# 4th_4G.net
KiCad netlist of a schematic drawn in Altium Designer
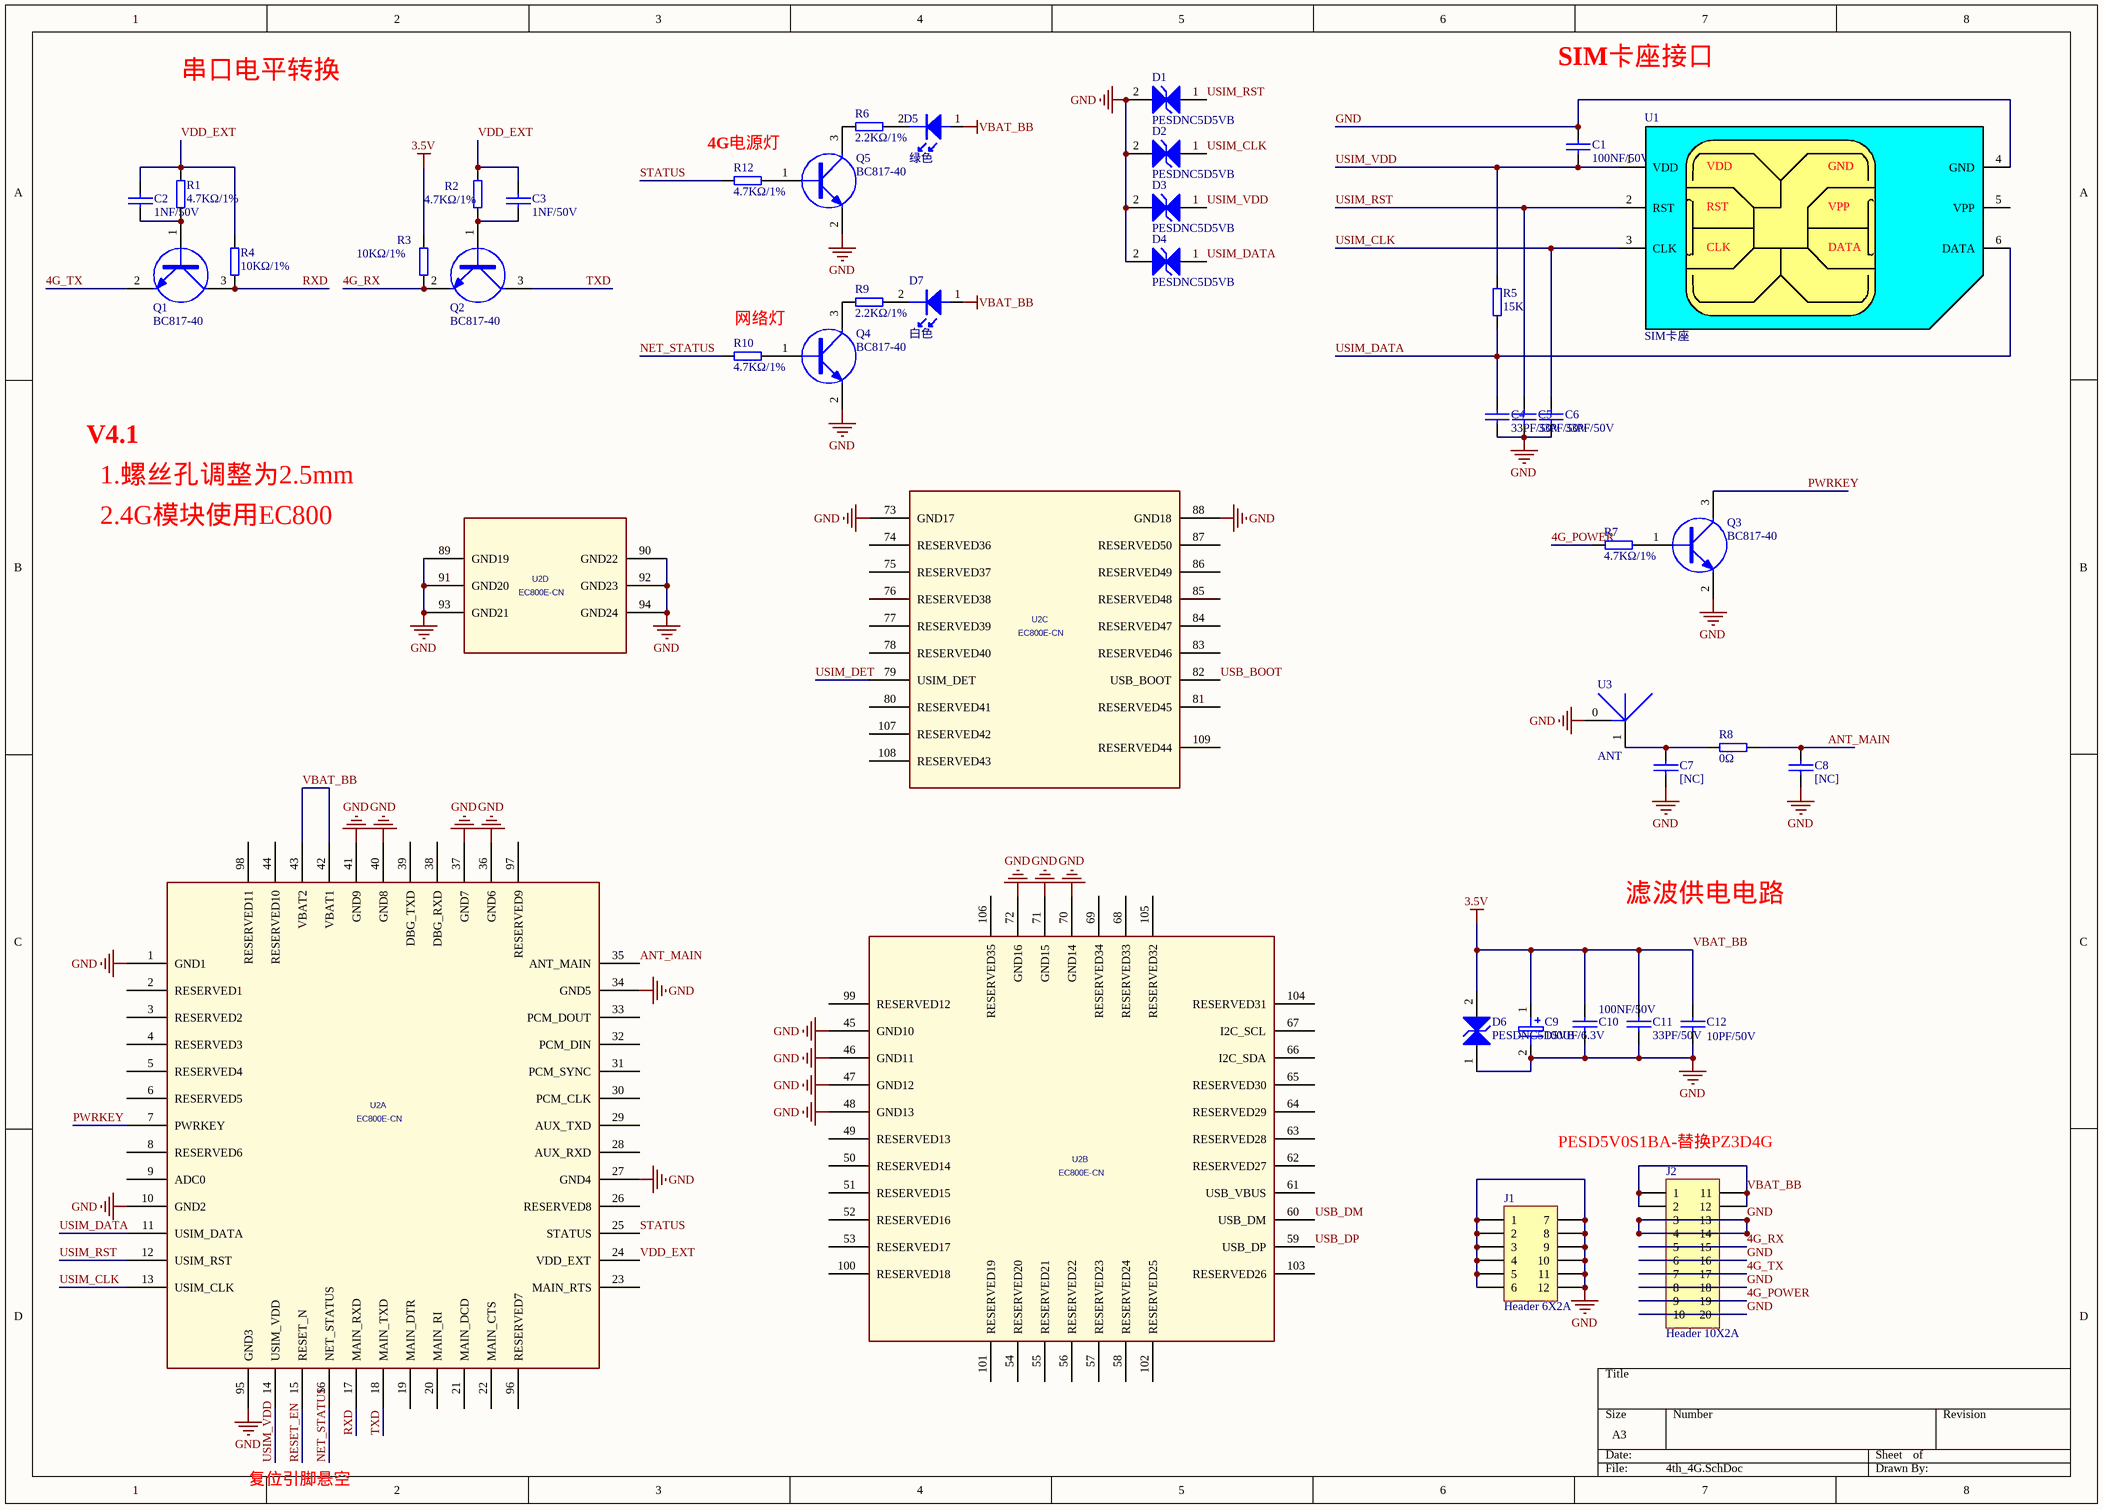
[diagram p0: 4th_4G.SchDoc]

(export (version "E")
  (design (tool "Eeschema 10.0.6"))
  (components
    (comp (ref "C1")
      (value "100NF/50V")
      (footprint "0603_C")
      (description "无极性电容")
      (libsource (lib "Integrated_Library") (part "CAP"))
    )
    (comp (ref "C2")
      (value "1NF/50V")
      (footprint "0603_C")
      (description "无极性电容")
      (libsource (lib "Integrated_Library") (part "CAP"))
    )
    (comp (ref "C3")
      (value "1NF/50V")
      (footprint "0603_C")
      (description "无极性电容")
      (libsource (lib "Integrated_Library") (part "CAP"))
    )
    (comp (ref "C4")
      (value "33PF/50V")
      (footprint "0603_C")
      (description "无极性电容")
      (libsource (lib "Integrated_Library") (part "CAP"))
    )
    (comp (ref "C5")
      (value "33PF/50V")
      (footprint "0603_C")
      (description "无极性电容")
      (libsource (lib "Integrated_Library") (part "CAP"))
    )
    (comp (ref "C6")
      (value "33PF/50V")
      (footprint "0603_C")
      (description "无极性电容")
      (libsource (lib "Integrated_Library") (part "CAP"))
    )
    (comp (ref "C7")
      (value "[NC]")
      (footprint "0603_C")
      (description "无极性电容")
      (libsource (lib "Integrated_Library") (part "CAP"))
    )
    (comp (ref "C8")
      (value "[NC]")
      (footprint "0603_C")
      (description "无极性电容")
      (libsource (lib "Integrated_Library") (part "CAP"))
    )
    (comp (ref "C9")
      (value "100UF/6.3V")
      (footprint "CASE-B_3528")
      (description "钽电容")
      (libsource (lib "Integrated_Library") (part "CAP POLAR"))
    )
    (comp (ref "C10")
      (value "100NF/50V")
      (footprint "0603_C")
      (description "无极性电容")
      (libsource (lib "Integrated_Library") (part "CAP"))
    )
    (comp (ref "C11")
      (value "33PF/50V")
      (footprint "0603_C")
      (description "无极性电容")
      (libsource (lib "Integrated_Library") (part "CAP"))
    )
    (comp (ref "C12")
      (value "10PF/50V")
      (footprint "0603_C")
      (description "无极性电容")
      (libsource (lib "Integrated_Library") (part "CAP"))
    )
    (comp (ref "D1")
      (value "PESDNC5D5VB")
      (footprint "SOD-523")
      (description "TVS 瞬态抑制二极管")
      (fields (field (name "PUBLISHER") "Altium Limited"))
      (libsource (lib "Integrated_Library") (part "TVS"))
    )
    (comp (ref "D2")
      (value "PESDNC5D5VB")
      (footprint "SOD-523")
      (description "TVS 瞬态抑制二极管")
      (fields (field (name "PUBLISHER") "Altium Limited"))
      (libsource (lib "Integrated_Library") (part "TVS"))
    )
    (comp (ref "D3")
      (value "PESDNC5D5VB")
      (footprint "SOD-523")
      (description "TVS 瞬态抑制二极管")
      (fields (field (name "PUBLISHER") "Altium Limited"))
      (libsource (lib "Integrated_Library") (part "TVS"))
    )
    (comp (ref "D4")
      (value "PESDNC5D5VB")
      (footprint "SOD-523")
      (description "TVS 瞬态抑制二极管")
      (fields (field (name "PUBLISHER") "Altium Limited"))
      (libsource (lib "Integrated_Library") (part "TVS"))
    )
    (comp (ref "D5")
      (value "绿色")
      (footprint "0603_D")
      (description "发光二极管")
      (libsource (lib "Integrated_Library") (part "LED"))
    )
    (comp (ref "D6")
      (value "PESDNC5D5VB")
      (footprint "SOD-523")
      (description "TVS 瞬态抑制二极管")
      (fields (field (name "PUBLISHER") "Altium Limited"))
      (libsource (lib "Integrated_Library") (part "TVS"))
    )
    (comp (ref "D7")
      (value "白色")
      (footprint "0603_D")
      (description "发光二极管")
      (libsource (lib "Integrated_Library") (part "LED"))
    )
    (comp (ref "J1")
      (value "Header 6X2A")
      (footprint "HDR2X6_CEN")
      (description "Header, 6-Pin, Dual row")
      (fields (field (name "PUBLISHER") "Altium Limited"))
      (libsource (lib "Miscellaneous Connectors") (part "Header 6X2A"))
    )
    (comp (ref "J2")
      (value "Header 10X2A")
      (footprint "HDR2X10_CEN")
      (description "Header, 10-Pin, Dual row")
      (fields (field (name "PUBLISHER") "Altium Limited"))
      (libsource (lib "Miscellaneous Connectors") (part "Header 10X2A"))
    )
    (comp (ref "Q1")
      (value "BC817-40")
      (footprint "SOT-23-3")
      (description "NPN")
      (libsource (lib "Integrated_Library") (part "S8050"))
    )
    (comp (ref "Q2")
      (value "BC817-40")
      (footprint "SOT-23-3")
      (description "NPN")
      (libsource (lib "Integrated_Library") (part "S8050"))
    )
    (comp (ref "Q3")
      (value "BC817-40")
      (footprint "SOT-23-3")
      (description "NPN三极管")
      (libsource (lib "Integrated_Library") (part "BC817-40"))
    )
    (comp (ref "Q4")
      (value "BC817-40")
      (footprint "SOT-23-3")
      (description "NPN")
      (libsource (lib "Integrated_Library") (part "S8050"))
    )
    (comp (ref "Q5")
      (value "BC817-40")
      (footprint "SOT-23-3")
      (description "NPN")
      (libsource (lib "Integrated_Library") (part "S8050"))
    )
    (comp (ref "R1")
      (value "4.7KΩ/1%")
      (footprint "0603_R")
      (description "电阻")
      (libsource (lib "Integrated_Library") (part "RES2"))
    )
    (comp (ref "R2")
      (value "4.7KΩ/1%")
      (footprint "0603_R")
      (description "电阻")
      (libsource (lib "Integrated_Library") (part "RES2"))
    )
    (comp (ref "R3")
      (value "10KΩ/1%")
      (footprint "0603_R")
      (description "电阻")
      (libsource (lib "Integrated_Library") (part "RES2"))
    )
    (comp (ref "R4")
      (value "10KΩ/1%")
      (footprint "0603_R")
      (description "电阻")
      (libsource (lib "Integrated_Library") (part "RES2"))
    )
    (comp (ref "R5")
      (value "15K")
      (footprint "0603_R")
      (description "电阻")
      (libsource (lib "Integrated_Library") (part "RES2"))
    )
    (comp (ref "R6")
      (value "2.2KΩ/1%")
      (footprint "0603_R")
      (description "电阻")
      (libsource (lib "Integrated_Library") (part "RES2"))
    )
    (comp (ref "R7")
      (value "4.7KΩ/1%")
      (footprint "0603_R")
      (description "电阻")
      (libsource (lib "Integrated_Library") (part "RES2"))
    )
    (comp (ref "R8")
      (value "0Ω")
      (footprint "0603_R")
      (description "电阻")
      (libsource (lib "Integrated_Library") (part "RES2"))
    )
    (comp (ref "R9")
      (value "2.2KΩ/1%")
      (footprint "0603_R")
      (description "电阻")
      (libsource (lib "Integrated_Library") (part "RES2"))
    )
    (comp (ref "R10")
      (value "4.7KΩ/1%")
      (footprint "0603_R")
      (description "电阻")
      (libsource (lib "Integrated_Library") (part "RES2"))
    )
    (comp (ref "R12")
      (value "4.7KΩ/1%")
      (footprint "0603_R")
      (description "电阻")
      (libsource (lib "Integrated_Library") (part "RES2"))
    )
    (comp (ref "U1")
      (value "SIM卡座")
      (footprint "SIM卡座-NANO掀盖式")
      (description "无保护引脚SIM卡座")
      (libsource (lib "MyLib Schlib") (part "SIM卡座"))
    )
    (comp (ref "U2")
      (value "EC800E-CN")
      (footprint "EC800E-CN")
      (description "EC800E-CN Module 109PIN 15.8x17.7mm H2.4mm RO")
      (fields (field (name "MANUFACTURER") "Quectel"))
      (libsource (lib "Integrated_Library") (part "EC800E-CN"))
    )
    (comp (ref "U3")
      (value "ANT")
      (footprint "SMA-KWE/弯头")
      (description "天线座")
      (libsource (lib "Integrated_Library") (part "ANT"))
    )
  )
  (nets
    (net (code "1") (name "/4G_POWER") (class "Default")
      (node (ref "J2") (pin "19") (pinfunction "19_19") (pintype "passive"))
      (node (ref "J2") (pin "9") (pinfunction "9_9") (pintype "passive"))
      (node (ref "R7") (pin "1") (pinfunction "1_1") (pintype "passive"))
    )
    (net (code "2") (name "/4G_RX") (class "Default")
      (node (ref "J2") (pin "15") (pinfunction "15_15") (pintype "passive"))
      (node (ref "J2") (pin "5") (pinfunction "5_5") (pintype "passive"))
      (node (ref "Q2") (pin "2") (pinfunction "2_2") (pintype "passive"))
      (node (ref "R3") (pin "1") (pinfunction "1_1") (pintype "passive"))
    )
    (net (code "3") (name "/4G_TX") (class "Default")
      (node (ref "J2") (pin "17") (pinfunction "17_17") (pintype "passive"))
      (node (ref "J2") (pin "7") (pinfunction "7_7") (pintype "passive"))
      (node (ref "Q1") (pin "2") (pinfunction "2_2") (pintype "passive"))
    )
    (net (code "4") (name "/ANT_MAIN") (class "Default")
      (node (ref "C8") (pin "1") (pinfunction "1_1") (pintype "passive"))
      (node (ref "R8") (pin "2") (pinfunction "2_2") (pintype "passive"))
      (node (ref "U2") (pin "35") (pinfunction "ANT_MAIN_35") (pintype "passive"))
    )
    (net (code "5") (name "/NET_STATUS") (class "Default")
      (node (ref "R10") (pin "1") (pinfunction "1_1") (pintype "passive"))
      (node (ref "U2") (pin "16") (pinfunction "NET_STATUS_16") (pintype "passive"))
    )
    (net (code "6") (name "/PWRKEY") (class "Default")
      (node (ref "Q3") (pin "3") (pinfunction "3_3") (pintype "passive"))
      (node (ref "U2") (pin "7") (pinfunction "PWRKEY_7") (pintype "passive"))
    )
    (net (code "7") (name "/RESET_EN") (class "Default")
      (node (ref "U2") (pin "15") (pinfunction "RESET_N_15") (pintype "passive"))
    )
    (net (code "8") (name "/RXD") (class "Default")
      (node (ref "Q1") (pin "3") (pinfunction "3_3") (pintype "passive"))
      (node (ref "R4") (pin "1") (pinfunction "1_1") (pintype "passive"))
      (node (ref "U2") (pin "17") (pinfunction "MAIN_RXD_17") (pintype "passive"))
    )
    (net (code "9") (name "/STATUS") (class "Default")
      (node (ref "R12") (pin "1") (pinfunction "1_1") (pintype "passive"))
      (node (ref "U2") (pin "25") (pinfunction "STATUS_25") (pintype "passive"))
    )
    (net (code "10") (name "/TXD") (class "Default")
      (node (ref "Q2") (pin "3") (pinfunction "3_3") (pintype "passive"))
      (node (ref "U2") (pin "18") (pinfunction "MAIN_TXD_18") (pintype "passive"))
    )
    (net (code "11") (name "/USB_BOOT") (class "Default")
      (node (ref "U2") (pin "82") (pinfunction "USB_BOOT_82") (pintype "passive"))
    )
    (net (code "12") (name "/USB_DM") (class "Default")
      (node (ref "U2") (pin "60") (pinfunction "USB_DM_60") (pintype "passive"))
    )
    (net (code "13") (name "/USB_DP") (class "Default")
      (node (ref "U2") (pin "59") (pinfunction "USB_DP_59") (pintype "passive"))
    )
    (net (code "14") (name "/USIM_CLK") (class "Default")
      (node (ref "C6") (pin "1") (pinfunction "1_1") (pintype "passive"))
      (node (ref "D2") (pin "1") (pinfunction "1_1") (pintype "passive"))
      (node (ref "U1") (pin "3") (pinfunction "CLK_3") (pintype "passive"))
      (node (ref "U2") (pin "13") (pinfunction "USIM_CLK_13") (pintype "passive"))
    )
    (net (code "15") (name "/USIM_DATA") (class "Default")
      (node (ref "C4") (pin "1") (pinfunction "1_1") (pintype "passive"))
      (node (ref "D4") (pin "1") (pinfunction "1_1") (pintype "passive"))
      (node (ref "R5") (pin "1") (pinfunction "1_1") (pintype "passive"))
      (node (ref "U1") (pin "6") (pinfunction "DATA_6") (pintype "passive"))
      (node (ref "U2") (pin "11") (pinfunction "USIM_DATA_11") (pintype "passive"))
    )
    (net (code "16") (name "/USIM_DET") (class "Default")
      (node (ref "U2") (pin "79") (pinfunction "USIM_DET_79") (pintype "passive"))
    )
    (net (code "17") (name "/USIM_RST") (class "Default")
      (node (ref "C5") (pin "1") (pinfunction "1_1") (pintype "passive"))
      (node (ref "D1") (pin "1") (pinfunction "1_1") (pintype "passive"))
      (node (ref "U1") (pin "2") (pinfunction "RST_2") (pintype "passive"))
      (node (ref "U2") (pin "12") (pinfunction "USIM_RST_12") (pintype "passive"))
    )
    (net (code "18") (name "/USIM_VDD") (class "Default")
      (node (ref "C1") (pin "2") (pinfunction "2_2") (pintype "passive"))
      (node (ref "D3") (pin "1") (pinfunction "1_1") (pintype "passive"))
      (node (ref "R5") (pin "2") (pinfunction "2_2") (pintype "passive"))
      (node (ref "U1") (pin "1") (pinfunction "VDD_1") (pintype "passive"))
      (node (ref "U2") (pin "14") (pinfunction "USIM_VDD_14") (pintype "passive"))
    )
    (net (code "19") (name "/VDD_EXT") (class "Default")
      (node (ref "C2") (pin "1") (pinfunction "1_1") (pintype "passive"))
      (node (ref "C3") (pin "1") (pinfunction "1_1") (pintype "passive"))
      (node (ref "R1") (pin "2") (pinfunction "2_2") (pintype "passive"))
      (node (ref "R2") (pin "2") (pinfunction "2_2") (pintype "passive"))
      (node (ref "R4") (pin "2") (pinfunction "2_2") (pintype "passive"))
      (node (ref "U2") (pin "24") (pinfunction "VDD_EXT_24") (pintype "passive"))
    )
    (net (code "20") (name "3.5V") (class "Default")
      (node (ref "C10") (pin "1") (pinfunction "1_1") (pintype "passive"))
      (node (ref "C11") (pin "1") (pinfunction "1_1") (pintype "passive"))
      (node (ref "C12") (pin "1") (pinfunction "1_1") (pintype "passive"))
      (node (ref "C9") (pin "1") (pinfunction "1_1") (pintype "passive"))
      (node (ref "D5") (pin "1") (pinfunction "1_1") (pintype "passive"))
      (node (ref "D6") (pin "2") (pinfunction "K_2") (pintype "passive"))
      (node (ref "D7") (pin "1") (pinfunction "1_1") (pintype "passive"))
      (node (ref "J2") (pin "1") (pinfunction "1_1") (pintype "passive"))
      (node (ref "J2") (pin "11") (pinfunction "11_11") (pintype "passive"))
      (node (ref "J2") (pin "12") (pinfunction "12_12") (pintype "passive"))
      (node (ref "J2") (pin "2") (pinfunction "2_2") (pintype "passive"))
      (node (ref "R3") (pin "2") (pinfunction "2_2") (pintype "passive"))
      (node (ref "U2") (pin "42") (pinfunction "VBAT1_42") (pintype "passive"))
      (node (ref "U2") (pin "43") (pinfunction "VBAT2_43") (pintype "passive"))
    )
    (net (code "21") (name "GND") (class "Default")
      (node (ref "C1") (pin "1") (pinfunction "1_1") (pintype "passive"))
      (node (ref "C10") (pin "2") (pinfunction "2_2") (pintype "passive"))
      (node (ref "C11") (pin "2") (pinfunction "2_2") (pintype "passive"))
      (node (ref "C12") (pin "2") (pinfunction "2_2") (pintype "passive"))
      (node (ref "C4") (pin "2") (pinfunction "2_2") (pintype "passive"))
      (node (ref "C5") (pin "2") (pinfunction "2_2") (pintype "passive"))
      (node (ref "C6") (pin "2") (pinfunction "2_2") (pintype "passive"))
      (node (ref "C7") (pin "2") (pinfunction "2_2") (pintype "passive"))
      (node (ref "C8") (pin "2") (pinfunction "2_2") (pintype "passive"))
      (node (ref "C9") (pin "2") (pinfunction "2_2") (pintype "passive"))
      (node (ref "D1") (pin "2") (pinfunction "K_2") (pintype "passive"))
      (node (ref "D2") (pin "2") (pinfunction "K_2") (pintype "passive"))
      (node (ref "D3") (pin "2") (pinfunction "K_2") (pintype "passive"))
      (node (ref "D4") (pin "2") (pinfunction "K_2") (pintype "passive"))
      (node (ref "D6") (pin "1") (pinfunction "1_1") (pintype "passive"))
      (node (ref "J1") (pin "1") (pinfunction "1_1") (pintype "passive"))
      (node (ref "J1") (pin "10") (pinfunction "10_10") (pintype "passive"))
      (node (ref "J1") (pin "11") (pinfunction "11_11") (pintype "passive"))
      (node (ref "J1") (pin "12") (pinfunction "12_12") (pintype "passive"))
      (node (ref "J1") (pin "2") (pinfunction "2_2") (pintype "passive"))
      (node (ref "J1") (pin "3") (pinfunction "3_3") (pintype "passive"))
      (node (ref "J1") (pin "4") (pinfunction "4_4") (pintype "passive"))
      (node (ref "J1") (pin "5") (pinfunction "5_5") (pintype "passive"))
      (node (ref "J1") (pin "6") (pinfunction "6_6") (pintype "passive"))
      (node (ref "J1") (pin "7") (pinfunction "7_7") (pintype "passive"))
      (node (ref "J1") (pin "8") (pinfunction "8_8") (pintype "passive"))
      (node (ref "J1") (pin "9") (pinfunction "9_9") (pintype "passive"))
      (node (ref "J2") (pin "10") (pinfunction "10_10") (pintype "passive"))
      (node (ref "J2") (pin "13") (pinfunction "13_13") (pintype "passive"))
      (node (ref "J2") (pin "14") (pinfunction "14_14") (pintype "passive"))
      (node (ref "J2") (pin "16") (pinfunction "16_16") (pintype "passive"))
      (node (ref "J2") (pin "18") (pinfunction "18_18") (pintype "passive"))
      (node (ref "J2") (pin "20") (pinfunction "20_20") (pintype "passive"))
      (node (ref "J2") (pin "3") (pinfunction "3_3") (pintype "passive"))
      (node (ref "J2") (pin "4") (pinfunction "4_4") (pintype "passive"))
      (node (ref "J2") (pin "6") (pinfunction "6_6") (pintype "passive"))
      (node (ref "J2") (pin "8") (pinfunction "8_8") (pintype "passive"))
      (node (ref "Q3") (pin "2") (pinfunction "2_2") (pintype "passive"))
      (node (ref "Q4") (pin "2") (pinfunction "2_2") (pintype "passive"))
      (node (ref "Q5") (pin "2") (pinfunction "2_2") (pintype "passive"))
      (node (ref "U1") (pin "4") (pinfunction "GND_4") (pintype "passive"))
      (node (ref "U2") (pin "1") (pinfunction "GND1_1") (pintype "passive"))
      (node (ref "U2") (pin "10") (pinfunction "GND2_10") (pintype "passive"))
      (node (ref "U2") (pin "27") (pinfunction "GND4_27") (pintype "passive"))
      (node (ref "U2") (pin "34") (pinfunction "GND5_34") (pintype "passive"))
      (node (ref "U2") (pin "36") (pinfunction "GND6_36") (pintype "passive"))
      (node (ref "U2") (pin "37") (pinfunction "GND7_37") (pintype "passive"))
      (node (ref "U2") (pin "40") (pinfunction "GND8_40") (pintype "passive"))
      (node (ref "U2") (pin "41") (pinfunction "GND9_41") (pintype "passive"))
      (node (ref "U2") (pin "45") (pinfunction "GND10_45") (pintype "passive"))
      (node (ref "U2") (pin "46") (pinfunction "GND11_46") (pintype "passive"))
      (node (ref "U2") (pin "47") (pinfunction "GND12_47") (pintype "passive"))
      (node (ref "U2") (pin "48") (pinfunction "GND13_48") (pintype "passive"))
      (node (ref "U2") (pin "70") (pinfunction "GND14_70") (pintype "passive"))
      (node (ref "U2") (pin "71") (pinfunction "GND15_71") (pintype "passive"))
      (node (ref "U2") (pin "72") (pinfunction "GND16_72") (pintype "passive"))
      (node (ref "U2") (pin "73") (pinfunction "GND17_73") (pintype "passive"))
      (node (ref "U2") (pin "88") (pinfunction "GND18_88") (pintype "passive"))
      (node (ref "U2") (pin "89") (pinfunction "GND19_89") (pintype "passive"))
      (node (ref "U2") (pin "90") (pinfunction "GND22_90") (pintype "passive"))
      (node (ref "U2") (pin "91") (pinfunction "GND20_91") (pintype "passive"))
      (node (ref "U2") (pin "92") (pinfunction "GND23_92") (pintype "passive"))
      (node (ref "U2") (pin "93") (pinfunction "GND21_93") (pintype "passive"))
      (node (ref "U2") (pin "94") (pinfunction "GND24_94") (pintype "passive"))
      (node (ref "U2") (pin "95") (pinfunction "GND3_95") (pintype "passive"))
      (node (ref "U3") (pin "0") (pinfunction "0_0") (pintype "passive"))
    )
    (net (code "22") (name "Net-(C2-Pad2)") (class "Default")
      (node (ref "C2") (pin "2") (pinfunction "2_2") (pintype "passive"))
      (node (ref "Q1") (pin "1") (pinfunction "1_1") (pintype "passive"))
      (node (ref "R1") (pin "1") (pinfunction "1_1") (pintype "passive"))
    )
    (net (code "23") (name "Net-(C3-Pad2)") (class "Default")
      (node (ref "C3") (pin "2") (pinfunction "2_2") (pintype "passive"))
      (node (ref "Q2") (pin "1") (pinfunction "1_1") (pintype "passive"))
      (node (ref "R2") (pin "1") (pinfunction "1_1") (pintype "passive"))
    )
    (net (code "24") (name "Net-(C7-Pad1)") (class "Default")
      (node (ref "C7") (pin "1") (pinfunction "1_1") (pintype "passive"))
      (node (ref "R8") (pin "1") (pinfunction "1_1") (pintype "passive"))
      (node (ref "U3") (pin "1") (pinfunction "1_1") (pintype "passive"))
    )
    (net (code "25") (name "Net-(D5-Pad2)") (class "Default")
      (node (ref "D5") (pin "2") (pinfunction "2_2") (pintype "passive"))
      (node (ref "R6") (pin "1") (pinfunction "1_1") (pintype "passive"))
    )
    (net (code "26") (name "Net-(D7-Pad2)") (class "Default")
      (node (ref "D7") (pin "2") (pinfunction "2_2") (pintype "passive"))
      (node (ref "R9") (pin "1") (pinfunction "1_1") (pintype "passive"))
    )
    (net (code "27") (name "Net-(Q3-Pad1)") (class "Default")
      (node (ref "Q3") (pin "1") (pinfunction "1_1") (pintype "passive"))
      (node (ref "R7") (pin "2") (pinfunction "2_2") (pintype "passive"))
    )
    (net (code "28") (name "Net-(Q4-Pad1)") (class "Default")
      (node (ref "Q4") (pin "1") (pinfunction "1_1") (pintype "passive"))
      (node (ref "R10") (pin "2") (pinfunction "2_2") (pintype "passive"))
    )
    (net (code "29") (name "Net-(Q4-Pad3)") (class "Default")
      (node (ref "Q4") (pin "3") (pinfunction "3_3") (pintype "passive"))
      (node (ref "R9") (pin "2") (pinfunction "2_2") (pintype "passive"))
    )
    (net (code "30") (name "Net-(Q5-Pad1)") (class "Default")
      (node (ref "Q5") (pin "1") (pinfunction "1_1") (pintype "passive"))
      (node (ref "R12") (pin "2") (pinfunction "2_2") (pintype "passive"))
    )
    (net (code "31") (name "Net-(Q5-Pad3)") (class "Default")
      (node (ref "Q5") (pin "3") (pinfunction "3_3") (pintype "passive"))
      (node (ref "R6") (pin "2") (pinfunction "2_2") (pintype "passive"))
    )
    (net (code "32") (name "unconnected-(U1-VPP-Pad5)") (class "Default")
      (node (ref "U1") (pin "5") (pinfunction "VPP_5") (pintype "passive"))
    )
    (net (code "33") (name "unconnected-(U2A-ADC0-Pad9)") (class "Default")
      (node (ref "U2") (pin "9") (pinfunction "ADC0_9") (pintype "passive"))
    )
    (net (code "34") (name "unconnected-(U2A-AUX_RXD-Pad28)") (class "Default")
      (node (ref "U2") (pin "28") (pinfunction "AUX_RXD_28") (pintype "passive"))
    )
    (net (code "35") (name "unconnected-(U2A-AUX_TXD-Pad29)") (class "Default")
      (node (ref "U2") (pin "29") (pinfunction "AUX_TXD_29") (pintype "passive"))
    )
    (net (code "36") (name "unconnected-(U2A-DBG_RXD-Pad38)") (class "Default")
      (node (ref "U2") (pin "38") (pinfunction "DBG_RXD_38") (pintype "passive"))
    )
    (net (code "37") (name "unconnected-(U2A-DBG_TXD-Pad39)") (class "Default")
      (node (ref "U2") (pin "39") (pinfunction "DBG_TXD_39") (pintype "passive"))
    )
    (net (code "38") (name "unconnected-(U2A-MAIN_CTS-Pad22)") (class "Default")
      (node (ref "U2") (pin "22") (pinfunction "MAIN_CTS_22") (pintype "passive"))
    )
    (net (code "39") (name "unconnected-(U2A-MAIN_DCD-Pad21)") (class "Default")
      (node (ref "U2") (pin "21") (pinfunction "MAIN_DCD_21") (pintype "passive"))
    )
    (net (code "40") (name "unconnected-(U2A-MAIN_DTR-Pad19)") (class "Default")
      (node (ref "U2") (pin "19") (pinfunction "MAIN_DTR_19") (pintype "passive"))
    )
    (net (code "41") (name "unconnected-(U2A-MAIN_RI-Pad20)") (class "Default")
      (node (ref "U2") (pin "20") (pinfunction "MAIN_RI_20") (pintype "passive"))
    )
    (net (code "42") (name "unconnected-(U2A-MAIN_RTS-Pad23)") (class "Default")
      (node (ref "U2") (pin "23") (pinfunction "MAIN_RTS_23") (pintype "passive"))
    )
    (net (code "43") (name "unconnected-(U2A-PCM_CLK-Pad30)") (class "Default")
      (node (ref "U2") (pin "30") (pinfunction "PCM_CLK_30") (pintype "passive"))
    )
    (net (code "44") (name "unconnected-(U2A-PCM_DIN-Pad32)") (class "Default")
      (node (ref "U2") (pin "32") (pinfunction "PCM_DIN_32") (pintype "passive"))
    )
    (net (code "45") (name "unconnected-(U2A-PCM_DOUT-Pad33)") (class "Default")
      (node (ref "U2") (pin "33") (pinfunction "PCM_DOUT_33") (pintype "passive"))
    )
    (net (code "46") (name "unconnected-(U2A-PCM_SYNC-Pad31)") (class "Default")
      (node (ref "U2") (pin "31") (pinfunction "PCM_SYNC_31") (pintype "passive"))
    )
    (net (code "47") (name "unconnected-(U2A-RESERVED1-Pad2)") (class "Default")
      (node (ref "U2") (pin "2") (pinfunction "RESERVED1_2") (pintype "passive"))
    )
    (net (code "48") (name "unconnected-(U2A-RESERVED2-Pad3)") (class "Default")
      (node (ref "U2") (pin "3") (pinfunction "RESERVED2_3") (pintype "passive"))
    )
    (net (code "49") (name "unconnected-(U2A-RESERVED3-Pad4)") (class "Default")
      (node (ref "U2") (pin "4") (pinfunction "RESERVED3_4") (pintype "passive"))
    )
    (net (code "50") (name "unconnected-(U2A-RESERVED4-Pad5)") (class "Default")
      (node (ref "U2") (pin "5") (pinfunction "RESERVED4_5") (pintype "passive"))
    )
    (net (code "51") (name "unconnected-(U2A-RESERVED5-Pad6)") (class "Default")
      (node (ref "U2") (pin "6") (pinfunction "RESERVED5_6") (pintype "passive"))
    )
    (net (code "52") (name "unconnected-(U2A-RESERVED6-Pad8)") (class "Default")
      (node (ref "U2") (pin "8") (pinfunction "RESERVED6_8") (pintype "passive"))
    )
    (net (code "53") (name "unconnected-(U2A-RESERVED7-Pad96)") (class "Default")
      (node (ref "U2") (pin "96") (pinfunction "RESERVED7_96") (pintype "passive"))
    )
    (net (code "54") (name "unconnected-(U2A-RESERVED8-Pad26)") (class "Default")
      (node (ref "U2") (pin "26") (pinfunction "RESERVED8_26") (pintype "passive"))
    )
    (net (code "55") (name "unconnected-(U2A-RESERVED9-Pad97)") (class "Default")
      (node (ref "U2") (pin "97") (pinfunction "RESERVED9_97") (pintype "passive"))
    )
    (net (code "56") (name "unconnected-(U2A-RESERVED10-Pad44)") (class "Default")
      (node (ref "U2") (pin "44") (pinfunction "RESERVED10_44") (pintype "passive"))
    )
    (net (code "57") (name "unconnected-(U2A-RESERVED11-Pad98)") (class "Default")
      (node (ref "U2") (pin "98") (pinfunction "RESERVED11_98") (pintype "passive"))
    )
    (net (code "58") (name "unconnected-(U2B-I2C_SCL-Pad67)") (class "Default")
      (node (ref "U2") (pin "67") (pinfunction "I2C_SCL_67") (pintype "passive"))
    )
    (net (code "59") (name "unconnected-(U2B-I2C_SDA-Pad66)") (class "Default")
      (node (ref "U2") (pin "66") (pinfunction "I2C_SDA_66") (pintype "passive"))
    )
    (net (code "60") (name "unconnected-(U2B-RESERVED12-Pad99)") (class "Default")
      (node (ref "U2") (pin "99") (pinfunction "RESERVED12_99") (pintype "passive"))
    )
    (net (code "61") (name "unconnected-(U2B-RESERVED13-Pad49)") (class "Default")
      (node (ref "U2") (pin "49") (pinfunction "RESERVED13_49") (pintype "passive"))
    )
    (net (code "62") (name "unconnected-(U2B-RESERVED14-Pad50)") (class "Default")
      (node (ref "U2") (pin "50") (pinfunction "RESERVED14_50") (pintype "passive"))
    )
    (net (code "63") (name "unconnected-(U2B-RESERVED15-Pad51)") (class "Default")
      (node (ref "U2") (pin "51") (pinfunction "RESERVED15_51") (pintype "passive"))
    )
    (net (code "64") (name "unconnected-(U2B-RESERVED16-Pad52)") (class "Default")
      (node (ref "U2") (pin "52") (pinfunction "RESERVED16_52") (pintype "passive"))
    )
    (net (code "65") (name "unconnected-(U2B-RESERVED17-Pad53)") (class "Default")
      (node (ref "U2") (pin "53") (pinfunction "RESERVED17_53") (pintype "passive"))
    )
    (net (code "66") (name "unconnected-(U2B-RESERVED18-Pad100)") (class "Default")
      (node (ref "U2") (pin "100") (pinfunction "RESERVED18_100") (pintype "passive"))
    )
    (net (code "67") (name "unconnected-(U2B-RESERVED19-Pad101)") (class "Default")
      (node (ref "U2") (pin "101") (pinfunction "RESERVED19_101") (pintype "passive"))
    )
    (net (code "68") (name "unconnected-(U2B-RESERVED20-Pad54)") (class "Default")
      (node (ref "U2") (pin "54") (pinfunction "RESERVED20_54") (pintype "passive"))
    )
    (net (code "69") (name "unconnected-(U2B-RESERVED21-Pad55)") (class "Default")
      (node (ref "U2") (pin "55") (pinfunction "RESERVED21_55") (pintype "passive"))
    )
    (net (code "70") (name "unconnected-(U2B-RESERVED22-Pad56)") (class "Default")
      (node (ref "U2") (pin "56") (pinfunction "RESERVED22_56") (pintype "passive"))
    )
    (net (code "71") (name "unconnected-(U2B-RESERVED23-Pad57)") (class "Default")
      (node (ref "U2") (pin "57") (pinfunction "RESERVED23_57") (pintype "passive"))
    )
    (net (code "72") (name "unconnected-(U2B-RESERVED24-Pad58)") (class "Default")
      (node (ref "U2") (pin "58") (pinfunction "RESERVED24_58") (pintype "passive"))
    )
    (net (code "73") (name "unconnected-(U2B-RESERVED25-Pad102)") (class "Default")
      (node (ref "U2") (pin "102") (pinfunction "RESERVED25_102") (pintype "passive"))
    )
    (net (code "74") (name "unconnected-(U2B-RESERVED26-Pad103)") (class "Default")
      (node (ref "U2") (pin "103") (pinfunction "RESERVED26_103") (pintype "passive"))
    )
    (net (code "75") (name "unconnected-(U2B-RESERVED27-Pad62)") (class "Default")
      (node (ref "U2") (pin "62") (pinfunction "RESERVED27_62") (pintype "passive"))
    )
    (net (code "76") (name "unconnected-(U2B-RESERVED28-Pad63)") (class "Default")
      (node (ref "U2") (pin "63") (pinfunction "RESERVED28_63") (pintype "passive"))
    )
    (net (code "77") (name "unconnected-(U2B-RESERVED29-Pad64)") (class "Default")
      (node (ref "U2") (pin "64") (pinfunction "RESERVED29_64") (pintype "passive"))
    )
    (net (code "78") (name "unconnected-(U2B-RESERVED30-Pad65)") (class "Default")
      (node (ref "U2") (pin "65") (pinfunction "RESERVED30_65") (pintype "passive"))
    )
    (net (code "79") (name "unconnected-(U2B-RESERVED31-Pad104)") (class "Default")
      (node (ref "U2") (pin "104") (pinfunction "RESERVED31_104") (pintype "passive"))
    )
    (net (code "80") (name "unconnected-(U2B-RESERVED32-Pad105)") (class "Default")
      (node (ref "U2") (pin "105") (pinfunction "RESERVED32_105") (pintype "passive"))
    )
    (net (code "81") (name "unconnected-(U2B-RESERVED33-Pad68)") (class "Default")
      (node (ref "U2") (pin "68") (pinfunction "RESERVED33_68") (pintype "passive"))
    )
    (net (code "82") (name "unconnected-(U2B-RESERVED34-Pad69)") (class "Default")
      (node (ref "U2") (pin "69") (pinfunction "RESERVED34_69") (pintype "passive"))
    )
    (net (code "83") (name "unconnected-(U2B-RESERVED35-Pad106)") (class "Default")
      (node (ref "U2") (pin "106") (pinfunction "RESERVED35_106") (pintype "passive"))
    )
    (net (code "84") (name "unconnected-(U2B-USB_VBUS-Pad61)") (class "Default")
      (node (ref "U2") (pin "61") (pinfunction "USB_VBUS_61") (pintype "passive"))
    )
    (net (code "85") (name "unconnected-(U2C-RESERVED36-Pad74)") (class "Default")
      (node (ref "U2") (pin "74") (pinfunction "RESERVED36_74") (pintype "passive"))
    )
    (net (code "86") (name "unconnected-(U2C-RESERVED37-Pad75)") (class "Default")
      (node (ref "U2") (pin "75") (pinfunction "RESERVED37_75") (pintype "passive"))
    )
    (net (code "87") (name "unconnected-(U2C-RESERVED38-Pad76)") (class "Default")
      (node (ref "U2") (pin "76") (pinfunction "RESERVED38_76") (pintype "passive"))
    )
    (net (code "88") (name "unconnected-(U2C-RESERVED39-Pad77)") (class "Default")
      (node (ref "U2") (pin "77") (pinfunction "RESERVED39_77") (pintype "passive"))
    )
    (net (code "89") (name "unconnected-(U2C-RESERVED40-Pad78)") (class "Default")
      (node (ref "U2") (pin "78") (pinfunction "RESERVED40_78") (pintype "passive"))
    )
    (net (code "90") (name "unconnected-(U2C-RESERVED41-Pad80)") (class "Default")
      (node (ref "U2") (pin "80") (pinfunction "RESERVED41_80") (pintype "passive"))
    )
    (net (code "91") (name "unconnected-(U2C-RESERVED42-Pad107)") (class "Default")
      (node (ref "U2") (pin "107") (pinfunction "RESERVED42_107") (pintype "passive"))
    )
    (net (code "92") (name "unconnected-(U2C-RESERVED43-Pad108)") (class "Default")
      (node (ref "U2") (pin "108") (pinfunction "RESERVED43_108") (pintype "passive"))
    )
    (net (code "93") (name "unconnected-(U2C-RESERVED44-Pad109)") (class "Default")
      (node (ref "U2") (pin "109") (pinfunction "RESERVED44_109") (pintype "passive"))
    )
    (net (code "94") (name "unconnected-(U2C-RESERVED45-Pad81)") (class "Default")
      (node (ref "U2") (pin "81") (pinfunction "RESERVED45_81") (pintype "passive"))
    )
    (net (code "95") (name "unconnected-(U2C-RESERVED46-Pad83)") (class "Default")
      (node (ref "U2") (pin "83") (pinfunction "RESERVED46_83") (pintype "passive"))
    )
    (net (code "96") (name "unconnected-(U2C-RESERVED47-Pad84)") (class "Default")
      (node (ref "U2") (pin "84") (pinfunction "RESERVED47_84") (pintype "passive"))
    )
    (net (code "97") (name "unconnected-(U2C-RESERVED48-Pad85)") (class "Default")
      (node (ref "U2") (pin "85") (pinfunction "RESERVED48_85") (pintype "passive"))
    )
    (net (code "98") (name "unconnected-(U2C-RESERVED49-Pad86)") (class "Default")
      (node (ref "U2") (pin "86") (pinfunction "RESERVED49_86") (pintype "passive"))
    )
    (net (code "99") (name "unconnected-(U2C-RESERVED50-Pad87)") (class "Default")
      (node (ref "U2") (pin "87") (pinfunction "RESERVED50_87") (pintype "passive"))
    )
  )
)
